# SOM.net
KiCad netlist of a schematic drawn in Altium Designer
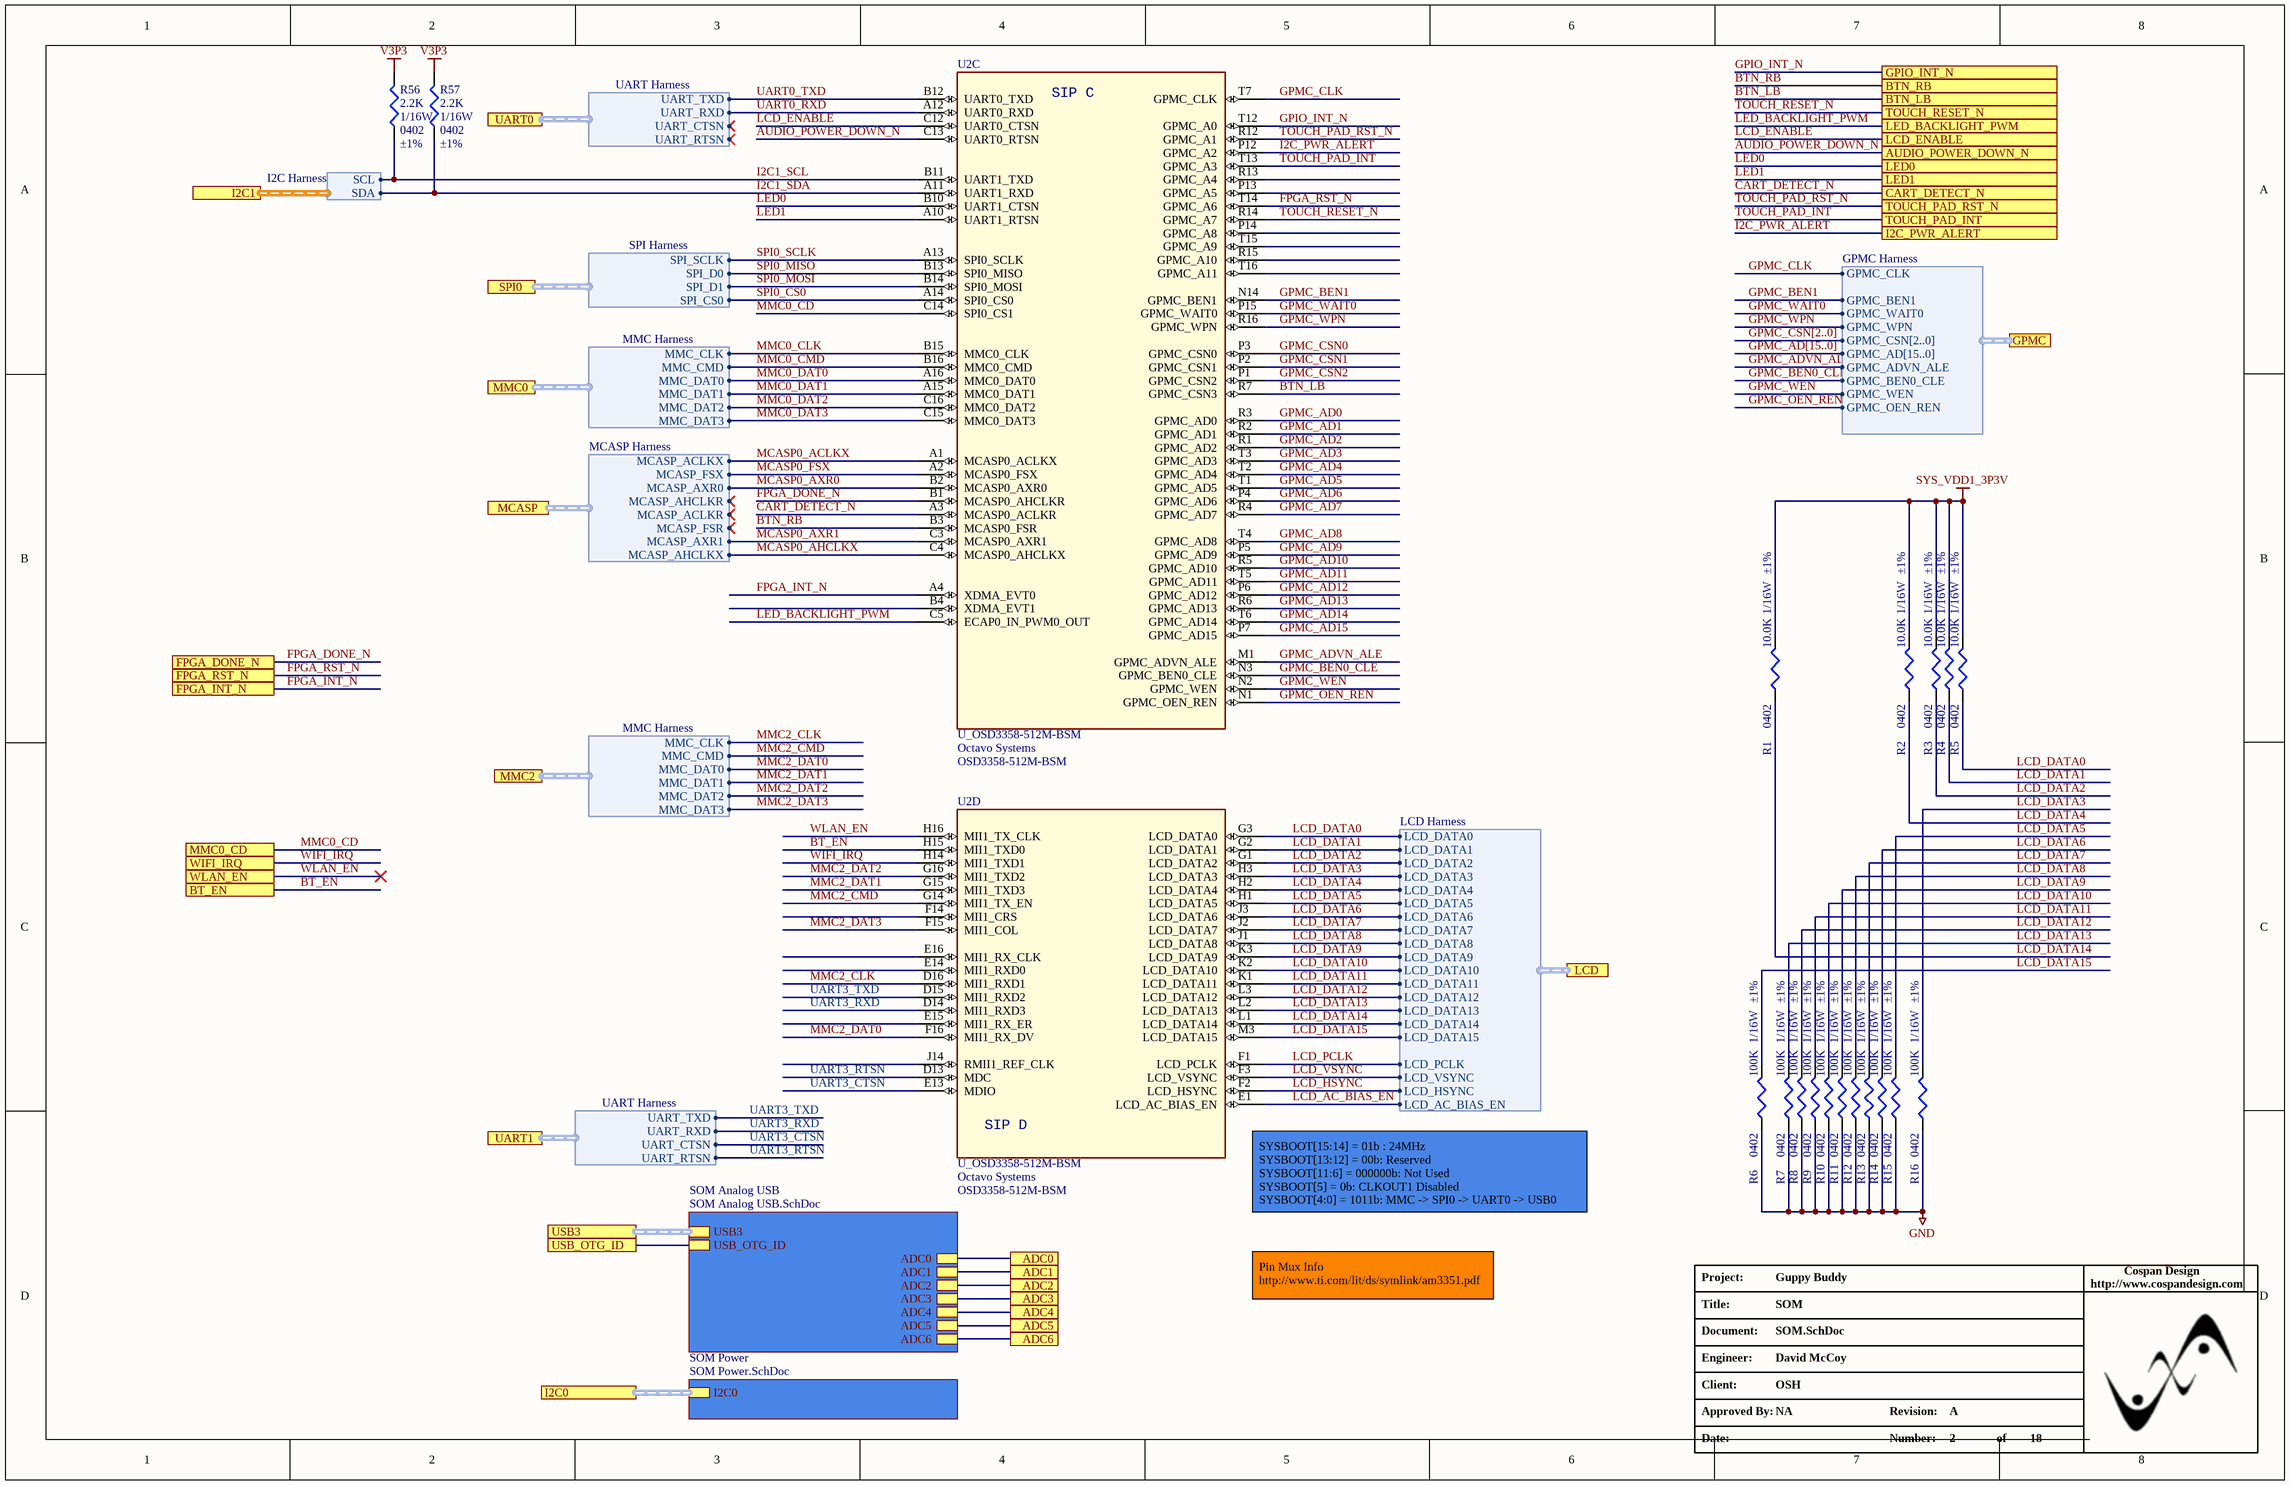
[diagram p0: SOM.SchDoc]

(export (version "E")
  (design (tool "Eeschema 10.0.6"))
  (components
    (comp (ref "R1")
      (value "R_0402_10.0K")
      (footprint "R_0402")
      (description "RES 10.0K OHM 1/16W 1% 0402 SMD")
      (fields
        (field (name "MANUFACTURER") "Stackpole Electronics Inc")
        (field (name "MANUFACTURER PART NUMBER") "RMCF0402FT10K0")
        (field (name "RESISTANCE IN OHMS") "10.0K")
        (field (name "POWER (WATTS)") "1/16W")
        (field (name "CASE") "0402")
        (field (name "TOLERANCE") "±1%")
      )
      (libsource (lib "Cospan Design") (part "R_0402_10.0K"))
    )
    (comp (ref "R2")
      (value "R_0402_10.0K")
      (footprint "R_0402")
      (description "RES 10.0K OHM 1/16W 1% 0402 SMD")
      (fields
        (field (name "MANUFACTURER") "Stackpole Electronics Inc")
        (field (name "MANUFACTURER PART NUMBER") "RMCF0402FT10K0")
        (field (name "RESISTANCE IN OHMS") "10.0K")
        (field (name "POWER (WATTS)") "1/16W")
        (field (name "CASE") "0402")
        (field (name "TOLERANCE") "±1%")
      )
      (libsource (lib "Cospan Design") (part "R_0402_10.0K"))
    )
    (comp (ref "R3")
      (value "R_0402_10.0K")
      (footprint "R_0402")
      (description "RES 10.0K OHM 1/16W 1% 0402 SMD")
      (fields
        (field (name "MANUFACTURER") "Stackpole Electronics Inc")
        (field (name "MANUFACTURER PART NUMBER") "RMCF0402FT10K0")
        (field (name "RESISTANCE IN OHMS") "10.0K")
        (field (name "POWER (WATTS)") "1/16W")
        (field (name "CASE") "0402")
        (field (name "TOLERANCE") "±1%")
      )
      (libsource (lib "Cospan Design") (part "R_0402_10.0K"))
    )
    (comp (ref "R4")
      (value "R_0402_10.0K")
      (footprint "R_0402")
      (description "RES 10.0K OHM 1/16W 1% 0402 SMD")
      (fields
        (field (name "MANUFACTURER") "Stackpole Electronics Inc")
        (field (name "MANUFACTURER PART NUMBER") "RMCF0402FT10K0")
        (field (name "RESISTANCE IN OHMS") "10.0K")
        (field (name "POWER (WATTS)") "1/16W")
        (field (name "CASE") "0402")
        (field (name "TOLERANCE") "±1%")
      )
      (libsource (lib "Cospan Design") (part "R_0402_10.0K"))
    )
    (comp (ref "R5")
      (value "R_0402_10.0K")
      (footprint "R_0402")
      (description "RES 10.0K OHM 1/16W 1% 0402 SMD")
      (fields
        (field (name "MANUFACTURER") "Stackpole Electronics Inc")
        (field (name "MANUFACTURER PART NUMBER") "RMCF0402FT10K0")
        (field (name "RESISTANCE IN OHMS") "10.0K")
        (field (name "POWER (WATTS)") "1/16W")
        (field (name "CASE") "0402")
        (field (name "TOLERANCE") "±1%")
      )
      (libsource (lib "Cospan Design") (part "R_0402_10.0K"))
    )
    (comp (ref "R6")
      (value "R_0402_100K")
      (footprint "R_0402")
      (description "RES SMD 100K OHM 1% 1/16W 0402")
      (fields
        (field (name "MANUFACTURER") "Yageo")
        (field (name "MANUFACTURER PART NUMBER") "RC0402FR-07100KL")
        (field (name "RESISTANCE IN OHMS") "100K")
        (field (name "POWER (WATTS)") "1/16W")
        (field (name "CASE") "0402")
        (field (name "TOLERANCE") "±1%")
      )
      (libsource (lib "Cospan Design") (part "R_0402_100K"))
    )
    (comp (ref "R7")
      (value "R_0402_100K")
      (footprint "R_0402")
      (description "RES SMD 100K OHM 1% 1/16W 0402")
      (fields
        (field (name "MANUFACTURER") "Yageo")
        (field (name "MANUFACTURER PART NUMBER") "RC0402FR-07100KL")
        (field (name "RESISTANCE IN OHMS") "100K")
        (field (name "POWER (WATTS)") "1/16W")
        (field (name "CASE") "0402")
        (field (name "TOLERANCE") "±1%")
      )
      (libsource (lib "Cospan Design") (part "R_0402_100K"))
    )
    (comp (ref "R8")
      (value "R_0402_100K")
      (footprint "R_0402")
      (description "RES SMD 100K OHM 1% 1/16W 0402")
      (fields
        (field (name "MANUFACTURER") "Yageo")
        (field (name "MANUFACTURER PART NUMBER") "RC0402FR-07100KL")
        (field (name "RESISTANCE IN OHMS") "100K")
        (field (name "POWER (WATTS)") "1/16W")
        (field (name "CASE") "0402")
        (field (name "TOLERANCE") "±1%")
      )
      (libsource (lib "Cospan Design") (part "R_0402_100K"))
    )
    (comp (ref "R9")
      (value "R_0402_100K")
      (footprint "R_0402")
      (description "RES SMD 100K OHM 1% 1/16W 0402")
      (fields
        (field (name "MANUFACTURER") "Yageo")
        (field (name "MANUFACTURER PART NUMBER") "RC0402FR-07100KL")
        (field (name "RESISTANCE IN OHMS") "100K")
        (field (name "POWER (WATTS)") "1/16W")
        (field (name "CASE") "0402")
        (field (name "TOLERANCE") "±1%")
      )
      (libsource (lib "Cospan Design") (part "R_0402_100K"))
    )
    (comp (ref "R10")
      (value "R_0402_100K")
      (footprint "R_0402")
      (description "RES SMD 100K OHM 1% 1/16W 0402")
      (fields
        (field (name "MANUFACTURER") "Yageo")
        (field (name "MANUFACTURER PART NUMBER") "RC0402FR-07100KL")
        (field (name "RESISTANCE IN OHMS") "100K")
        (field (name "POWER (WATTS)") "1/16W")
        (field (name "CASE") "0402")
        (field (name "TOLERANCE") "±1%")
      )
      (libsource (lib "Cospan Design") (part "R_0402_100K"))
    )
    (comp (ref "R11")
      (value "R_0402_100K")
      (footprint "R_0402")
      (description "RES SMD 100K OHM 1% 1/16W 0402")
      (fields
        (field (name "MANUFACTURER") "Yageo")
        (field (name "MANUFACTURER PART NUMBER") "RC0402FR-07100KL")
        (field (name "RESISTANCE IN OHMS") "100K")
        (field (name "POWER (WATTS)") "1/16W")
        (field (name "CASE") "0402")
        (field (name "TOLERANCE") "±1%")
      )
      (libsource (lib "Cospan Design") (part "R_0402_100K"))
    )
    (comp (ref "R12")
      (value "R_0402_100K")
      (footprint "R_0402")
      (description "RES SMD 100K OHM 1% 1/16W 0402")
      (fields
        (field (name "MANUFACTURER") "Yageo")
        (field (name "MANUFACTURER PART NUMBER") "RC0402FR-07100KL")
        (field (name "RESISTANCE IN OHMS") "100K")
        (field (name "POWER (WATTS)") "1/16W")
        (field (name "CASE") "0402")
        (field (name "TOLERANCE") "±1%")
      )
      (libsource (lib "Cospan Design") (part "R_0402_100K"))
    )
    (comp (ref "R13")
      (value "R_0402_100K")
      (footprint "R_0402")
      (description "RES SMD 100K OHM 1% 1/16W 0402")
      (fields
        (field (name "MANUFACTURER") "Yageo")
        (field (name "MANUFACTURER PART NUMBER") "RC0402FR-07100KL")
        (field (name "RESISTANCE IN OHMS") "100K")
        (field (name "POWER (WATTS)") "1/16W")
        (field (name "CASE") "0402")
        (field (name "TOLERANCE") "±1%")
      )
      (libsource (lib "Cospan Design") (part "R_0402_100K"))
    )
    (comp (ref "R14")
      (value "R_0402_100K")
      (footprint "R_0402")
      (description "RES SMD 100K OHM 1% 1/16W 0402")
      (fields
        (field (name "MANUFACTURER") "Yageo")
        (field (name "MANUFACTURER PART NUMBER") "RC0402FR-07100KL")
        (field (name "RESISTANCE IN OHMS") "100K")
        (field (name "POWER (WATTS)") "1/16W")
        (field (name "CASE") "0402")
        (field (name "TOLERANCE") "±1%")
      )
      (libsource (lib "Cospan Design") (part "R_0402_100K"))
    )
    (comp (ref "R15")
      (value "R_0402_100K")
      (footprint "R_0402")
      (description "RES SMD 100K OHM 1% 1/16W 0402")
      (fields
        (field (name "MANUFACTURER") "Yageo")
        (field (name "MANUFACTURER PART NUMBER") "RC0402FR-07100KL")
        (field (name "RESISTANCE IN OHMS") "100K")
        (field (name "POWER (WATTS)") "1/16W")
        (field (name "CASE") "0402")
        (field (name "TOLERANCE") "±1%")
      )
      (libsource (lib "Cospan Design") (part "R_0402_100K"))
    )
    (comp (ref "R16")
      (value "R_0402_100K")
      (footprint "R_0402")
      (description "RES SMD 100K OHM 1% 1/16W 0402")
      (fields
        (field (name "MANUFACTURER") "Yageo")
        (field (name "MANUFACTURER PART NUMBER") "RC0402FR-07100KL")
        (field (name "RESISTANCE IN OHMS") "100K")
        (field (name "POWER (WATTS)") "1/16W")
        (field (name "CASE") "0402")
        (field (name "TOLERANCE") "±1%")
      )
      (libsource (lib "Cospan Design") (part "R_0402_100K"))
    )
    (comp (ref "R56")
      (value "R_0402_2.2K")
      (footprint "R_0402")
      (description "RES SMD 2.2K OHM 1% 1/10W 0402")
      (fields
        (field (name "MANUFACTURER") "Panasonic Electronic Components")
        (field (name "MANUFACTURER PART NUMBER") "ERJ-2RKF2201X")
        (field (name "RESISTANCE IN OHMS") "2.2K")
        (field (name "POWER (WATTS)") "1/16W")
        (field (name "CASE") "0402")
        (field (name "TOLERANCE") "±1%")
      )
      (libsource (lib "Cospan Design") (part "R_0402_2.2K"))
    )
    (comp (ref "R57")
      (value "R_0402_2.2K")
      (footprint "R_0402")
      (description "RES SMD 2.2K OHM 1% 1/10W 0402")
      (fields
        (field (name "MANUFACTURER") "Panasonic Electronic Components")
        (field (name "MANUFACTURER PART NUMBER") "ERJ-2RKF2201X")
        (field (name "RESISTANCE IN OHMS") "2.2K")
        (field (name "POWER (WATTS)") "1/16W")
        (field (name "CASE") "0402")
        (field (name "TOLERANCE") "±1%")
      )
      (libsource (lib "Cospan Design") (part "R_0402_2.2K"))
    )
    (comp (ref "U2")
      (value "U_OSD3358-512M-BSM")
      (footprint "OSD335X-BGA-256")
      (fields
        (field (name "MANUFACTURER 1") "Octavo Systems")
        (field (name "MANUFACTURER PART NUMBER 1") "OSD3358-512M-BSM")
      )
      (libsource (lib "Cospan Design") (part "U_OSD3358-512M-BSM"))
    )
  )
  (nets
    (net (code "20") (name "/AUDIO_POWER_DOWN_N") (class "Default")
      (node (ref "U2") (pin "C13") (pinfunction "UART0_RTSN_C13") (pintype "bidirectional"))
    )
    (net (code "21") (name "/BTN_LB") (class "Default")
      (node (ref "U2") (pin "R7") (pinfunction "GPMC_CSN3_R7") (pintype "bidirectional"))
    )
    (net (code "22") (name "/BTN_RB") (class "Default")
      (node (ref "U2") (pin "B3") (pinfunction "MCASP0_FSR_B3") (pintype "bidirectional"))
    )
    (net (code "23") (name "/BT_EN") (class "Default")
      (node (ref "U2") (pin "H15") (pinfunction "MII1_TXD0_H15") (pintype "bidirectional"))
    )
    (net (code "24") (name "/CART_DETECT_N") (class "Default")
      (node (ref "U2") (pin "A3") (pinfunction "MCASP0_ACLKR_A3") (pintype "bidirectional"))
    )
    (net (code "25") (name "/FPGA_DONE_N") (class "Default")
      (node (ref "U2") (pin "B1") (pinfunction "MCASP0_AHCLKR_B1") (pintype "bidirectional"))
    )
    (net (code "26") (name "/FPGA_INT_N") (class "Default")
      (node (ref "U2") (pin "A4") (pinfunction "XDMA_EVT0_A4") (pintype "bidirectional"))
    )
    (net (code "27") (name "/FPGA_RST_N") (class "Default")
      (node (ref "U2") (pin "T14") (pinfunction "GPMC_A6_T14") (pintype "bidirectional"))
    )
    (net (code "28") (name "/GPIO_INT_N") (class "Default")
      (node (ref "U2") (pin "T12") (pinfunction "GPMC_A0_T12") (pintype "bidirectional"))
    )
    (net (code "29") (name "/GPMC_AD0") (class "Default")
      (node (ref "U2") (pin "R3") (pinfunction "GPMC_AD0_R3") (pintype "bidirectional"))
    )
    (net (code "30") (name "/GPMC_AD1") (class "Default")
      (node (ref "U2") (pin "R2") (pinfunction "GPMC_AD1_R2") (pintype "bidirectional"))
    )
    (net (code "31") (name "/GPMC_AD2") (class "Default")
      (node (ref "U2") (pin "R1") (pinfunction "GPMC_AD2_R1") (pintype "bidirectional"))
    )
    (net (code "32") (name "/GPMC_AD3") (class "Default")
      (node (ref "U2") (pin "T3") (pinfunction "GPMC_AD3_T3") (pintype "bidirectional"))
    )
    (net (code "33") (name "/GPMC_AD4") (class "Default")
      (node (ref "U2") (pin "T2") (pinfunction "GPMC_AD4_T2") (pintype "bidirectional"))
    )
    (net (code "34") (name "/GPMC_AD5") (class "Default")
      (node (ref "U2") (pin "T1") (pinfunction "GPMC_AD5_T1") (pintype "bidirectional"))
    )
    (net (code "35") (name "/GPMC_AD6") (class "Default")
      (node (ref "U2") (pin "P4") (pinfunction "GPMC_AD6_P4") (pintype "bidirectional"))
    )
    (net (code "36") (name "/GPMC_AD7") (class "Default")
      (node (ref "U2") (pin "R4") (pinfunction "GPMC_AD7_R4") (pintype "bidirectional"))
    )
    (net (code "37") (name "/GPMC_AD8") (class "Default")
      (node (ref "U2") (pin "T4") (pinfunction "GPMC_AD8_T4") (pintype "bidirectional"))
    )
    (net (code "38") (name "/GPMC_AD9") (class "Default")
      (node (ref "U2") (pin "P5") (pinfunction "GPMC_AD9_P5") (pintype "bidirectional"))
    )
    (net (code "39") (name "/GPMC_AD10") (class "Default")
      (node (ref "U2") (pin "R5") (pinfunction "GPMC_AD10_R5") (pintype "bidirectional"))
    )
    (net (code "40") (name "/GPMC_AD11") (class "Default")
      (node (ref "U2") (pin "T5") (pinfunction "GPMC_AD11_T5") (pintype "bidirectional"))
    )
    (net (code "41") (name "/GPMC_AD12") (class "Default")
      (node (ref "U2") (pin "P6") (pinfunction "GPMC_AD12_P6") (pintype "bidirectional"))
    )
    (net (code "42") (name "/GPMC_AD13") (class "Default")
      (node (ref "U2") (pin "R6") (pinfunction "GPMC_AD13_R6") (pintype "bidirectional"))
    )
    (net (code "43") (name "/GPMC_AD14") (class "Default")
      (node (ref "U2") (pin "T6") (pinfunction "GPMC_AD14_T6") (pintype "bidirectional"))
    )
    (net (code "44") (name "/GPMC_AD15") (class "Default")
      (node (ref "U2") (pin "P7") (pinfunction "GPMC_AD15_P7") (pintype "bidirectional"))
    )
    (net (code "45") (name "/GPMC_ADVN_ALE") (class "Default")
      (node (ref "U2") (pin "M1") (pinfunction "GPMC_ADVN_ALE_M1") (pintype "bidirectional"))
    )
    (net (code "47") (name "/GPMC_BEN0_CLE") (class "Default")
      (node (ref "U2") (pin "N3") (pinfunction "GPMC_BEN0_CLE_N3") (pintype "bidirectional"))
    )
    (net (code "48") (name "/GPMC_BEN1") (class "Default")
      (node (ref "U2") (pin "N14") (pinfunction "GPMC_BEN1_N14") (pintype "bidirectional"))
    )
    (net (code "49") (name "/GPMC_CLK") (class "Default")
      (node (ref "U2") (pin "T7") (pinfunction "GPMC_CLK_T7") (pintype "bidirectional"))
    )
    (net (code "50") (name "/GPMC_CSN0") (class "Default")
      (node (ref "U2") (pin "P3") (pinfunction "GPMC_CSN0_P3") (pintype "bidirectional"))
    )
    (net (code "51") (name "/GPMC_CSN1") (class "Default")
      (node (ref "U2") (pin "P2") (pinfunction "GPMC_CSN1_P2") (pintype "bidirectional"))
    )
    (net (code "52") (name "/GPMC_CSN2") (class "Default")
      (node (ref "U2") (pin "P1") (pinfunction "GPMC_CSN2_P1") (pintype "bidirectional"))
    )
    (net (code "54") (name "/GPMC_OEN_REN") (class "Default")
      (node (ref "U2") (pin "N1") (pinfunction "GPMC_OEN_REN_N1") (pintype "bidirectional"))
    )
    (net (code "55") (name "/GPMC_WAIT0") (class "Default")
      (node (ref "U2") (pin "P15") (pinfunction "GPMC_WAIT0_P15") (pintype "bidirectional"))
    )
    (net (code "56") (name "/GPMC_WEN") (class "Default")
      (node (ref "U2") (pin "N2") (pinfunction "GPMC_WEN_N2") (pintype "bidirectional"))
    )
    (net (code "57") (name "/GPMC_WPN") (class "Default")
      (node (ref "U2") (pin "R16") (pinfunction "GPMC_WPN_R16") (pintype "bidirectional"))
    )
    (net (code "59") (name "/I2C1_SCL") (class "Default")
      (node (ref "R56") (pin "2") (pinfunction "2_2") (pintype "passive"))
      (node (ref "U2") (pin "B11") (pinfunction "UART1_TXD_B11") (pintype "bidirectional"))
    )
    (net (code "60") (name "/I2C1_SDA") (class "Default")
      (node (ref "R57") (pin "2") (pinfunction "2_2") (pintype "passive"))
      (node (ref "U2") (pin "A11") (pinfunction "UART1_RXD_A11") (pintype "bidirectional"))
    )
    (net (code "61") (name "/I2C_PWR_ALERT") (class "Default")
      (node (ref "U2") (pin "P12") (pinfunction "GPMC_A2_P12") (pintype "bidirectional"))
    )
    (net (code "62") (name "/LCD_AC_BIAS_EN") (class "Default")
      (node (ref "U2") (pin "E1") (pinfunction "LCD_AC_BIAS_EN_E1") (pintype "bidirectional"))
    )
    (net (code "63") (name "/LCD_DATA0") (class "Default")
      (node (ref "R5") (pin "1") (pinfunction "1_1") (pintype "passive"))
      (node (ref "U2") (pin "G3") (pinfunction "LCD_DATA0_G3") (pintype "bidirectional"))
    )
    (net (code "64") (name "/LCD_DATA1") (class "Default")
      (node (ref "R4") (pin "1") (pinfunction "1_1") (pintype "passive"))
      (node (ref "U2") (pin "G2") (pinfunction "LCD_DATA1_G2") (pintype "bidirectional"))
    )
    (net (code "65") (name "/LCD_DATA2") (class "Default")
      (node (ref "R3") (pin "1") (pinfunction "1_1") (pintype "passive"))
      (node (ref "U2") (pin "G1") (pinfunction "LCD_DATA2_G1") (pintype "bidirectional"))
    )
    (net (code "66") (name "/LCD_DATA3") (class "Default")
      (node (ref "R16") (pin "1") (pinfunction "1_1") (pintype "passive"))
      (node (ref "U2") (pin "H3") (pinfunction "LCD_DATA3_H3") (pintype "bidirectional"))
    )
    (net (code "67") (name "/LCD_DATA4") (class "Default")
      (node (ref "R2") (pin "1") (pinfunction "1_1") (pintype "passive"))
      (node (ref "U2") (pin "H2") (pinfunction "LCD_DATA4_H2") (pintype "bidirectional"))
    )
    (net (code "68") (name "/LCD_DATA5") (class "Default")
      (node (ref "R15") (pin "1") (pinfunction "1_1") (pintype "passive"))
      (node (ref "U2") (pin "H1") (pinfunction "LCD_DATA5_H1") (pintype "bidirectional"))
    )
    (net (code "69") (name "/LCD_DATA6") (class "Default")
      (node (ref "R14") (pin "1") (pinfunction "1_1") (pintype "passive"))
      (node (ref "U2") (pin "J3") (pinfunction "LCD_DATA6_J3") (pintype "bidirectional"))
    )
    (net (code "70") (name "/LCD_DATA7") (class "Default")
      (node (ref "R13") (pin "1") (pinfunction "1_1") (pintype "passive"))
      (node (ref "U2") (pin "J2") (pinfunction "LCD_DATA7_J2") (pintype "bidirectional"))
    )
    (net (code "71") (name "/LCD_DATA8") (class "Default")
      (node (ref "R12") (pin "1") (pinfunction "1_1") (pintype "passive"))
      (node (ref "U2") (pin "J1") (pinfunction "LCD_DATA8_J1") (pintype "bidirectional"))
    )
    (net (code "72") (name "/LCD_DATA9") (class "Default")
      (node (ref "R11") (pin "1") (pinfunction "1_1") (pintype "passive"))
      (node (ref "U2") (pin "K3") (pinfunction "LCD_DATA9_K3") (pintype "bidirectional"))
    )
    (net (code "73") (name "/LCD_DATA10") (class "Default")
      (node (ref "R10") (pin "1") (pinfunction "1_1") (pintype "passive"))
      (node (ref "U2") (pin "K2") (pinfunction "LCD_DATA10_K2") (pintype "bidirectional"))
    )
    (net (code "74") (name "/LCD_DATA11") (class "Default")
      (node (ref "R9") (pin "1") (pinfunction "1_1") (pintype "passive"))
      (node (ref "U2") (pin "K1") (pinfunction "LCD_DATA11_K1") (pintype "bidirectional"))
    )
    (net (code "75") (name "/LCD_DATA12") (class "Default")
      (node (ref "R8") (pin "1") (pinfunction "1_1") (pintype "passive"))
      (node (ref "U2") (pin "L3") (pinfunction "LCD_DATA12_L3") (pintype "bidirectional"))
    )
    (net (code "76") (name "/LCD_DATA13") (class "Default")
      (node (ref "R7") (pin "1") (pinfunction "1_1") (pintype "passive"))
      (node (ref "U2") (pin "L2") (pinfunction "LCD_DATA13_L2") (pintype "bidirectional"))
    )
    (net (code "77") (name "/LCD_DATA14") (class "Default")
      (node (ref "R1") (pin "1") (pinfunction "1_1") (pintype "passive"))
      (node (ref "U2") (pin "L1") (pinfunction "LCD_DATA14_L1") (pintype "bidirectional"))
    )
    (net (code "78") (name "/LCD_DATA15") (class "Default")
      (node (ref "R6") (pin "1") (pinfunction "1_1") (pintype "passive"))
      (node (ref "U2") (pin "M3") (pinfunction "LCD_DATA15_M3") (pintype "bidirectional"))
    )
    (net (code "79") (name "/LCD_ENABLE") (class "Default")
      (node (ref "U2") (pin "C12") (pinfunction "UART0_CTSN_C12") (pintype "bidirectional"))
    )
    (net (code "80") (name "/LCD_HSYNC") (class "Default")
      (node (ref "U2") (pin "F2") (pinfunction "LCD_HSYNC_F2") (pintype "bidirectional"))
    )
    (net (code "81") (name "/LCD_PCLK") (class "Default")
      (node (ref "U2") (pin "F1") (pinfunction "LCD_PCLK_F1") (pintype "bidirectional"))
    )
    (net (code "82") (name "/LCD_VSYNC") (class "Default")
      (node (ref "U2") (pin "F3") (pinfunction "LCD_VSYNC_F3") (pintype "bidirectional"))
    )
    (net (code "83") (name "/LED0") (class "Default")
      (node (ref "U2") (pin "B10") (pinfunction "UART1_CTSN_B10") (pintype "bidirectional"))
    )
    (net (code "84") (name "/LED1") (class "Default")
      (node (ref "U2") (pin "A10") (pinfunction "UART1_RTSN_A10") (pintype "bidirectional"))
    )
    (net (code "85") (name "/LED_BACKLIGHT_PWM") (class "Default")
      (node (ref "U2") (pin "C5") (pinfunction "ECAP0_IN_PWM0_OUT_C5") (pintype "bidirectional"))
    )
    (net (code "86") (name "/MCASP0_ACLKX") (class "Default")
      (node (ref "U2") (pin "A1") (pinfunction "MCASP0_ACLKX_A1") (pintype "bidirectional"))
    )
    (net (code "87") (name "/MCASP0_AHCLKX") (class "Default")
      (node (ref "U2") (pin "C4") (pinfunction "MCASP0_AHCLKX_C4") (pintype "bidirectional"))
    )
    (net (code "88") (name "/MCASP0_AXR0") (class "Default")
      (node (ref "U2") (pin "B2") (pinfunction "MCASP0_AXR0_B2") (pintype "bidirectional"))
    )
    (net (code "89") (name "/MCASP0_AXR1") (class "Default")
      (node (ref "U2") (pin "C3") (pinfunction "MCASP0_AXR1_C3") (pintype "bidirectional"))
    )
    (net (code "90") (name "/MCASP0_FSX") (class "Default")
      (node (ref "U2") (pin "A2") (pinfunction "MCASP0_FSX_A2") (pintype "bidirectional"))
    )
    (net (code "91") (name "/MMC0_CD") (class "Default")
      (node (ref "U2") (pin "C14") (pinfunction "SPI0_CS1_C14") (pintype "bidirectional"))
    )
    (net (code "92") (name "/MMC0_CLK") (class "Default")
      (node (ref "U2") (pin "B15") (pinfunction "MMC0_CLK_B15") (pintype "bidirectional"))
    )
    (net (code "93") (name "/MMC0_CMD") (class "Default")
      (node (ref "U2") (pin "B16") (pinfunction "MMC0_CMD_B16") (pintype "bidirectional"))
    )
    (net (code "94") (name "/MMC0_DAT0") (class "Default")
      (node (ref "U2") (pin "A16") (pinfunction "MMC0_DAT0_A16") (pintype "bidirectional"))
    )
    (net (code "95") (name "/MMC0_DAT1") (class "Default")
      (node (ref "U2") (pin "A15") (pinfunction "MMC0_DAT1_A15") (pintype "bidirectional"))
    )
    (net (code "96") (name "/MMC0_DAT2") (class "Default")
      (node (ref "U2") (pin "C16") (pinfunction "MMC0_DAT2_C16") (pintype "bidirectional"))
    )
    (net (code "97") (name "/MMC0_DAT3") (class "Default")
      (node (ref "U2") (pin "C15") (pinfunction "MMC0_DAT3_C15") (pintype "bidirectional"))
    )
    (net (code "98") (name "/MMC2_CLK") (class "Default")
      (node (ref "U2") (pin "D16") (pinfunction "MII1_RXD1_D16") (pintype "bidirectional"))
    )
    (net (code "99") (name "/MMC2_CMD") (class "Default")
      (node (ref "U2") (pin "G14") (pinfunction "MII1_TX_EN_G14") (pintype "bidirectional"))
    )
    (net (code "100") (name "/MMC2_DAT0") (class "Default")
      (node (ref "U2") (pin "F16") (pinfunction "MII1_RX_DV_F16") (pintype "bidirectional"))
    )
    (net (code "101") (name "/MMC2_DAT1") (class "Default")
      (node (ref "U2") (pin "G15") (pinfunction "MII1_TXD3_G15") (pintype "bidirectional"))
    )
    (net (code "102") (name "/MMC2_DAT2") (class "Default")
      (node (ref "U2") (pin "G16") (pinfunction "MII1_TXD2_G16") (pintype "bidirectional"))
    )
    (net (code "103") (name "/MMC2_DAT3") (class "Default")
      (node (ref "U2") (pin "F15") (pinfunction "MII1_COL_F15") (pintype "bidirectional"))
    )
    (net (code "104") (name "/SPI0_CS0") (class "Default")
      (node (ref "U2") (pin "A14") (pinfunction "SPI0_CS0_A14") (pintype "bidirectional"))
    )
    (net (code "105") (name "/SPI0_MISO") (class "Default")
      (node (ref "U2") (pin "B13") (pinfunction "SPI0_MISO_B13") (pintype "bidirectional"))
    )
    (net (code "106") (name "/SPI0_MOSI") (class "Default")
      (node (ref "U2") (pin "B14") (pinfunction "SPI0_MOSI_B14") (pintype "bidirectional"))
    )
    (net (code "107") (name "/SPI0_SCLK") (class "Default")
      (node (ref "U2") (pin "A13") (pinfunction "SPI0_SCLK_A13") (pintype "bidirectional"))
    )
    (net (code "108") (name "/TOUCH_PAD_INT") (class "Default")
      (node (ref "U2") (pin "T13") (pinfunction "GPMC_A3_T13") (pintype "bidirectional"))
    )
    (net (code "109") (name "/TOUCH_PAD_RST_N") (class "Default")
      (node (ref "U2") (pin "R12") (pinfunction "GPMC_A1_R12") (pintype "bidirectional"))
    )
    (net (code "110") (name "/TOUCH_RESET_N") (class "Default")
      (node (ref "U2") (pin "R14") (pinfunction "GPMC_A7_R14") (pintype "bidirectional"))
    )
    (net (code "111") (name "/UART0_RXD") (class "Default")
      (node (ref "U2") (pin "A12") (pinfunction "UART0_RXD_A12") (pintype "bidirectional"))
    )
    (net (code "112") (name "/UART0_TXD") (class "Default")
      (node (ref "U2") (pin "B12") (pinfunction "UART0_TXD_B12") (pintype "bidirectional"))
    )
    (net (code "113") (name "/UART3_CTSN") (class "Default")
      (node (ref "U2") (pin "E13") (pinfunction "MDIO_E13") (pintype "bidirectional"))
    )
    (net (code "114") (name "/UART3_RTSN") (class "Default")
      (node (ref "U2") (pin "D13") (pinfunction "MDC_D13") (pintype "bidirectional"))
    )
    (net (code "115") (name "/UART3_RXD") (class "Default")
      (node (ref "U2") (pin "D14") (pinfunction "MII1_RXD3_D14") (pintype "bidirectional"))
    )
    (net (code "116") (name "/UART3_TXD") (class "Default")
      (node (ref "U2") (pin "D15") (pinfunction "MII1_RXD2_D15") (pintype "bidirectional"))
    )
    (net (code "119") (name "/WIFI_IRQ") (class "Default")
      (node (ref "U2") (pin "H14") (pinfunction "MII1_TXD1_H14") (pintype "bidirectional"))
    )
    (net (code "120") (name "/WLAN_EN") (class "Default")
      (node (ref "U2") (pin "H16") (pinfunction "MII1_TX_CLK_H16") (pintype "bidirectional"))
    )
    (net (code "128") (name "GND") (class "Default")
      (node (ref "R10") (pin "2") (pinfunction "2_2") (pintype "passive"))
      (node (ref "R11") (pin "2") (pinfunction "2_2") (pintype "passive"))
      (node (ref "R12") (pin "2") (pinfunction "2_2") (pintype "passive"))
      (node (ref "R13") (pin "2") (pinfunction "2_2") (pintype "passive"))
      (node (ref "R14") (pin "2") (pinfunction "2_2") (pintype "passive"))
      (node (ref "R15") (pin "2") (pinfunction "2_2") (pintype "passive"))
      (node (ref "R16") (pin "2") (pinfunction "2_2") (pintype "passive"))
      (node (ref "R6") (pin "2") (pinfunction "2_2") (pintype "passive"))
      (node (ref "R7") (pin "2") (pinfunction "2_2") (pintype "passive"))
      (node (ref "R8") (pin "2") (pinfunction "2_2") (pintype "passive"))
      (node (ref "R9") (pin "2") (pinfunction "2_2") (pintype "passive"))
    )
    (net (code "129") (name "SYS_VDD1_3P3V") (class "Default")
      (node (ref "R1") (pin "2") (pinfunction "2_2") (pintype "passive"))
      (node (ref "R2") (pin "2") (pinfunction "2_2") (pintype "passive"))
      (node (ref "R3") (pin "2") (pinfunction "2_2") (pintype "passive"))
      (node (ref "R4") (pin "2") (pinfunction "2_2") (pintype "passive"))
      (node (ref "R5") (pin "2") (pinfunction "2_2") (pintype "passive"))
    )
    (net (code "130") (name "V3P3") (class "Default")
      (node (ref "R56") (pin "1") (pinfunction "1_1") (pintype "passive"))
      (node (ref "R57") (pin "1") (pinfunction "1_1") (pintype "passive"))
    )
    (net (code "131") (name "unconnected-(U2C-GPMC_A4-PadR13)") (class "Default")
      (node (ref "U2") (pin "R13") (pinfunction "GPMC_A4_R13") (pintype "bidirectional"))
    )
    (net (code "132") (name "unconnected-(U2C-GPMC_A5-PadP13)") (class "Default")
      (node (ref "U2") (pin "P13") (pinfunction "GPMC_A5_P13") (pintype "bidirectional"))
    )
    (net (code "133") (name "unconnected-(U2C-GPMC_A8-PadP14)") (class "Default")
      (node (ref "U2") (pin "P14") (pinfunction "GPMC_A8_P14") (pintype "bidirectional"))
    )
    (net (code "134") (name "unconnected-(U2C-GPMC_A9-PadT15)") (class "Default")
      (node (ref "U2") (pin "T15") (pinfunction "GPMC_A9_T15") (pintype "bidirectional"))
    )
    (net (code "135") (name "unconnected-(U2C-GPMC_A10-PadR15)") (class "Default")
      (node (ref "U2") (pin "R15") (pinfunction "GPMC_A10_R15") (pintype "bidirectional"))
    )
    (net (code "136") (name "unconnected-(U2C-GPMC_A11-PadT16)") (class "Default")
      (node (ref "U2") (pin "T16") (pinfunction "GPMC_A11_T16") (pintype "bidirectional"))
    )
    (net (code "137") (name "unconnected-(U2C-XDMA_EVT1-PadB4)") (class "Default")
      (node (ref "U2") (pin "B4") (pinfunction "XDMA_EVT1_B4") (pintype "bidirectional"))
    )
    (net (code "138") (name "unconnected-(U2D-MII1_CRS-PadF14)") (class "Default")
      (node (ref "U2") (pin "F14") (pinfunction "MII1_CRS_F14") (pintype "bidirectional"))
    )
    (net (code "139") (name "unconnected-(U2D-MII1_RXD0-PadE14)") (class "Default")
      (node (ref "U2") (pin "E14") (pinfunction "MII1_RXD0_E14") (pintype "bidirectional"))
    )
    (net (code "140") (name "unconnected-(U2D-MII1_RX_CLK-PadE16)") (class "Default")
      (node (ref "U2") (pin "E16") (pinfunction "MII1_RX_CLK_E16") (pintype "bidirectional"))
    )
    (net (code "141") (name "unconnected-(U2D-MII1_RX_ER-PadE15)") (class "Default")
      (node (ref "U2") (pin "E15") (pinfunction "MII1_RX_ER_E15") (pintype "bidirectional"))
    )
    (net (code "142") (name "unconnected-(U2D-RMII1_REF_CLK-PadJ14)") (class "Default")
      (node (ref "U2") (pin "J14") (pinfunction "RMII1_REF_CLK_J14") (pintype "bidirectional"))
    )
  )
)
